# VCA.net
KiCad netlist of a schematic drawn in Altium Designer
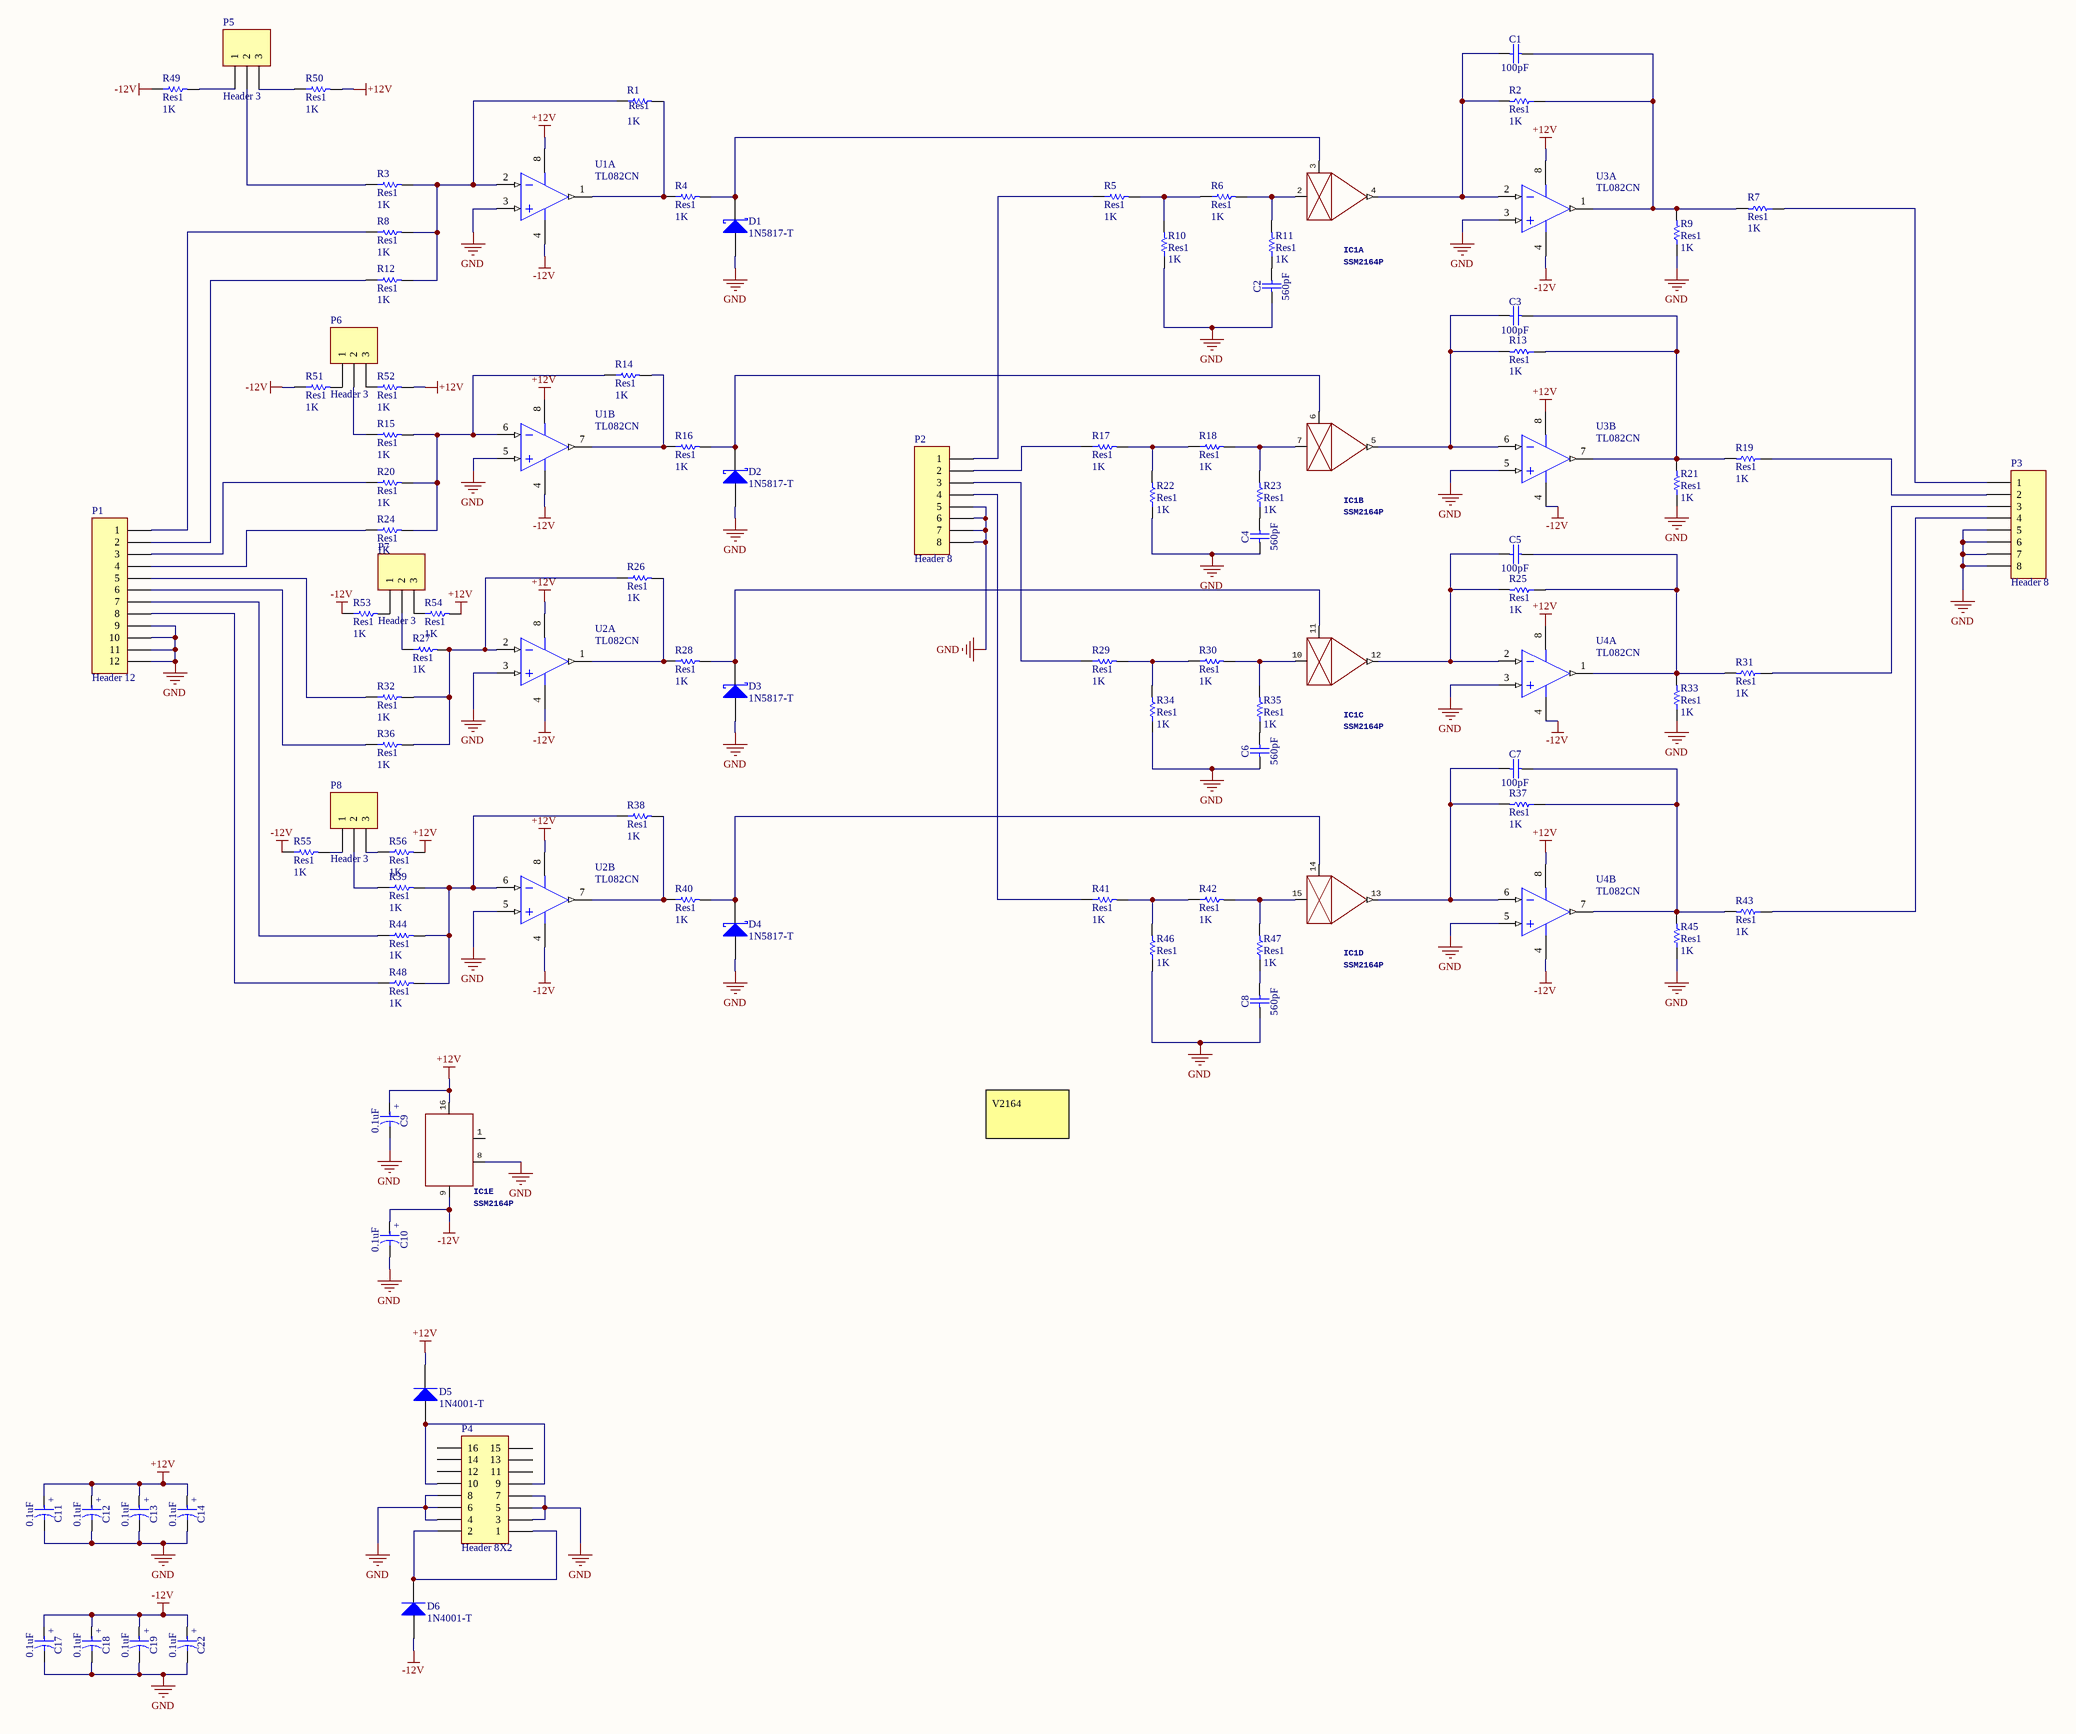
[diagram p0: VCA.SchDoc]

(export (version "E")
  (design (tool "Eeschema 10.0.6"))
  (components
    (comp (ref "C1")
      (value "100pF")
      (footprint "CAPRR508-254X381X584")
      (description "Non-polarised capacitor")
      (fields
        (field (name "PART NUMBER") "CCR_100PF_100V_5%_C0G_508-254X381X584")
        (field (name "VOLTAGE") "100VDC")
        (field (name "AUTHOR") "CERN DEM JLC")
      )
      (libsource (lib "Capacitors") (part "Capacitor - non polarized"))
    )
    (comp (ref "C2")
      (value "560pF")
      (footprint "CAPRR254-254X381X381")
      (description "Non-polarised capacitor")
      (fields
        (field (name "PART NUMBER") "CCR_560PF_100V_5%_C0G_254-254X381X381")
        (field (name "VOLTAGE") "100VDC")
        (field (name "AUTHOR") "CERN DEM JLC")
      )
      (libsource (lib "Capacitors") (part "Capacitor - non polarized"))
    )
    (comp (ref "C3")
      (value "100pF")
      (footprint "CAPRR508-254X381X584")
      (description "Non-polarised capacitor")
      (fields
        (field (name "PART NUMBER") "CCR_100PF_100V_5%_C0G_508-254X381X584")
        (field (name "VOLTAGE") "100VDC")
        (field (name "AUTHOR") "CERN DEM JLC")
      )
      (libsource (lib "Capacitors") (part "Capacitor - non polarized"))
    )
    (comp (ref "C4")
      (value "560pF")
      (footprint "CAPRR254-254X381X381")
      (description "Non-polarised capacitor")
      (fields
        (field (name "PART NUMBER") "CCR_560PF_100V_5%_C0G_254-254X381X381")
        (field (name "VOLTAGE") "100VDC")
        (field (name "AUTHOR") "CERN DEM JLC")
      )
      (libsource (lib "Capacitors") (part "Capacitor - non polarized"))
    )
    (comp (ref "C5")
      (value "100pF")
      (footprint "CAPRR508-254X381X584")
      (description "Non-polarised capacitor")
      (fields
        (field (name "PART NUMBER") "CCR_100PF_100V_5%_C0G_508-254X381X584")
        (field (name "VOLTAGE") "100VDC")
        (field (name "AUTHOR") "CERN DEM JLC")
      )
      (libsource (lib "Capacitors") (part "Capacitor - non polarized"))
    )
    (comp (ref "C6")
      (value "560pF")
      (footprint "CAPRR254-254X381X381")
      (description "Non-polarised capacitor")
      (fields
        (field (name "PART NUMBER") "CCR_560PF_100V_5%_C0G_254-254X381X381")
        (field (name "VOLTAGE") "100VDC")
        (field (name "AUTHOR") "CERN DEM JLC")
      )
      (libsource (lib "Capacitors") (part "Capacitor - non polarized"))
    )
    (comp (ref "C7")
      (value "100pF")
      (footprint "CAPRR508-254X381X584")
      (description "Non-polarised capacitor")
      (fields
        (field (name "PART NUMBER") "CCR_100PF_100V_5%_C0G_508-254X381X584")
        (field (name "VOLTAGE") "100VDC")
        (field (name "AUTHOR") "CERN DEM JLC")
      )
      (libsource (lib "Capacitors") (part "Capacitor - non polarized"))
    )
    (comp (ref "C8")
      (value "560pF")
      (footprint "CAPRR254-254X381X381")
      (description "Non-polarised capacitor")
      (fields
        (field (name "PART NUMBER") "CCR_560PF_100V_5%_C0G_254-254X381X381")
        (field (name "VOLTAGE") "100VDC")
        (field (name "AUTHOR") "CERN DEM JLC")
      )
      (libsource (lib "Capacitors") (part "Capacitor - non polarized"))
    )
    (comp (ref "C9")
      (value "0.1uF")
      (footprint "CAPPRB508-450x850")
      (description "Polarised capacitor")
      (fields
        (field (name "PART NUMBER") "CTEB_0.1UF_35V_10%_508-450X850")
        (field (name "VOLTAGE") "35V")
        (field (name "AUTHOR") "CERN DEM JLC")
      )
      (libsource (lib "Capacitors") (part "Capacitor - polarized"))
    )
    (comp (ref "C10")
      (value "0.1uF")
      (footprint "CAPPRB508-450x850")
      (description "Polarised capacitor")
      (fields
        (field (name "PART NUMBER") "CTEB_0.1UF_35V_10%_508-450X850")
        (field (name "VOLTAGE") "35V")
        (field (name "AUTHOR") "CERN DEM JLC")
      )
      (libsource (lib "Capacitors") (part "Capacitor - polarized"))
    )
    (comp (ref "C11")
      (value "0.1uF")
      (footprint "CAPPRB508-450x850")
      (description "Polarised capacitor")
      (fields
        (field (name "PART NUMBER") "CTEB_0.1UF_35V_10%_508-450X850")
        (field (name "VOLTAGE") "35V")
        (field (name "AUTHOR") "CERN DEM JLC")
      )
      (libsource (lib "Capacitors") (part "Capacitor - polarized"))
    )
    (comp (ref "C12")
      (value "0.1uF")
      (footprint "CAPPRB508-450x850")
      (description "Polarised capacitor")
      (fields
        (field (name "PART NUMBER") "CTEB_0.1UF_35V_10%_508-450X850")
        (field (name "VOLTAGE") "35V")
        (field (name "AUTHOR") "CERN DEM JLC")
      )
      (libsource (lib "Capacitors") (part "Capacitor - polarized"))
    )
    (comp (ref "C13")
      (value "0.1uF")
      (footprint "CAPPRB508-450x850")
      (description "Polarised capacitor")
      (fields
        (field (name "PART NUMBER") "CTEB_0.1UF_35V_10%_508-450X850")
        (field (name "VOLTAGE") "35V")
        (field (name "AUTHOR") "CERN DEM JLC")
      )
      (libsource (lib "Capacitors") (part "Capacitor - polarized"))
    )
    (comp (ref "C14")
      (value "0.1uF")
      (footprint "CAPPRB508-450x850")
      (description "Polarised capacitor")
      (fields
        (field (name "PART NUMBER") "CTEB_0.1UF_35V_10%_508-450X850")
        (field (name "VOLTAGE") "35V")
        (field (name "AUTHOR") "CERN DEM JLC")
      )
      (libsource (lib "Capacitors") (part "Capacitor - polarized"))
    )
    (comp (ref "C17")
      (value "0.1uF")
      (footprint "CAPPRB508-450x850")
      (description "Polarised capacitor")
      (fields
        (field (name "PART NUMBER") "CTEB_0.1UF_35V_10%_508-450X850")
        (field (name "VOLTAGE") "35V")
        (field (name "AUTHOR") "CERN DEM JLC")
      )
      (libsource (lib "Capacitors") (part "Capacitor - polarized"))
    )
    (comp (ref "C18")
      (value "0.1uF")
      (footprint "CAPPRB508-450x850")
      (description "Polarised capacitor")
      (fields
        (field (name "PART NUMBER") "CTEB_0.1UF_35V_10%_508-450X850")
        (field (name "VOLTAGE") "35V")
        (field (name "AUTHOR") "CERN DEM JLC")
      )
      (libsource (lib "Capacitors") (part "Capacitor - polarized"))
    )
    (comp (ref "C19")
      (value "0.1uF")
      (footprint "CAPPRB508-450x850")
      (description "Polarised capacitor")
      (fields
        (field (name "PART NUMBER") "CTEB_0.1UF_35V_10%_508-450X850")
        (field (name "VOLTAGE") "35V")
        (field (name "AUTHOR") "CERN DEM JLC")
      )
      (libsource (lib "Capacitors") (part "Capacitor - polarized"))
    )
    (comp (ref "C22")
      (value "0.1uF")
      (footprint "CAPPRB508-450x850")
      (description "Polarised capacitor")
      (fields
        (field (name "PART NUMBER") "CTEB_0.1UF_35V_10%_508-450X850")
        (field (name "VOLTAGE") "35V")
        (field (name "AUTHOR") "CERN DEM JLC")
      )
      (libsource (lib "Capacitors") (part "Capacitor - polarized"))
    )
    (comp (ref "D1")
      (value "1N5817-T")
      (footprint "DIOD-DO-41-P-2")
      (description "Schottky Barrier Rectifier, 1 A, 20 V, -65 to 125 degC, 2-Pin DO-41, RoHS, Tape and Reel")
      (fields (field (name "MANUFACTURER") "DiodesIncorporated"))
      (libsource (lib "Altium Content Vault") (part "DSKY-AK-2"))
    )
    (comp (ref "D2")
      (value "1N5817-T")
      (footprint "DIOD-DO-41-P-2")
      (description "Schottky Barrier Rectifier, 1 A, 20 V, -65 to 125 degC, 2-Pin DO-41, RoHS, Tape and Reel")
      (fields (field (name "MANUFACTURER") "DiodesIncorporated"))
      (libsource (lib "Altium Content Vault") (part "DSKY-AK-2"))
    )
    (comp (ref "D3")
      (value "1N5817-T")
      (footprint "DIOD-DO-41-P-2")
      (description "Schottky Barrier Rectifier, 1 A, 20 V, -65 to 125 degC, 2-Pin DO-41, RoHS, Tape and Reel")
      (fields (field (name "MANUFACTURER") "DiodesIncorporated"))
      (libsource (lib "Altium Content Vault") (part "DSKY-AK-2"))
    )
    (comp (ref "D4")
      (value "1N5817-T")
      (footprint "DIOD-DO-41-P-2")
      (description "Schottky Barrier Rectifier, 1 A, 20 V, -65 to 125 degC, 2-Pin DO-41, RoHS, Tape and Reel")
      (fields (field (name "MANUFACTURER") "DiodesIncorporated"))
      (libsource (lib "Altium Content Vault") (part "DSKY-AK-2"))
    )
    (comp (ref "D5")
      (value "1N4001-T")
      (footprint "DIOD-DO-41-P-2_V")
      (description "1.0 A Rectifier, 15 pF, 50 V, -65 to 150 degC, 2-Pin DO-41 Plastic, RoHS, Tape and Reel")
      (fields (field (name "MANUFACTURER") "Diodes Inc"))
      (libsource (lib "Altium Content Vault") (part "DIOD-D-A1K2-2"))
    )
    (comp (ref "D6")
      (value "1N4001-T")
      (footprint "DIOD-DO-41-P-2_V")
      (description "1.0 A Rectifier, 15 pF, 50 V, -65 to 150 degC, 2-Pin DO-41 Plastic, RoHS, Tape and Reel")
      (fields (field (name "MANUFACTURER") "Diodes Inc"))
      (libsource (lib "Altium Content Vault") (part "DIOD-D-A1K2-2"))
    )
    (comp (ref "IC1") (value "SSM2164P") (footprint "DIL16") (libsource (lib "ssm2164_2") (part "SSM2164P")))
    (comp (ref "P1")
      (value "Header 12")
      (footprint "HDR1X12")
      (description "Header, 12-Pin")
      (fields (field (name "PUBLISHER") "Altium Limited"))
      (libsource (lib "Miscellaneous Connectors") (part "Header 12"))
    )
    (comp (ref "P2")
      (value "Header 8")
      (footprint "HDR1X8")
      (description "Header, 8-Pin")
      (fields (field (name "PUBLISHER") "Altium Limited"))
      (libsource (lib "Miscellaneous Connectors") (part "Header 8"))
    )
    (comp (ref "P3")
      (value "Header 8")
      (footprint "HDR1X8")
      (description "Header, 8-Pin")
      (fields (field (name "PUBLISHER") "Altium Limited"))
      (libsource (lib "") (part "Header 8_1"))
    )
    (comp (ref "P4")
      (value "Header 8X2")
      (footprint "HDR2X8")
      (description "Header, 8-Pin, Dual row")
      (fields (field (name "PUBLISHER") "Altium Limited"))
      (libsource (lib "Miscellaneous Connectors") (part "Header 8X2"))
    )
    (comp (ref "P5")
      (value "Header 3")
      (footprint "HDR1X3")
      (description "Header, 3-Pin")
      (fields (field (name "PUBLISHER") "Altium Limited"))
      (libsource (lib "Miscellaneous Connectors") (part "Header 3"))
    )
    (comp (ref "P6")
      (value "Header 3")
      (footprint "HDR1X3")
      (description "Header, 3-Pin")
      (fields (field (name "PUBLISHER") "Altium Limited"))
      (libsource (lib "Miscellaneous Connectors") (part "Header 3"))
    )
    (comp (ref "P7")
      (value "Header 3")
      (footprint "HDR1X3")
      (description "Header, 3-Pin")
      (fields (field (name "PUBLISHER") "Altium Limited"))
      (libsource (lib "Miscellaneous Connectors") (part "Header 3"))
    )
    (comp (ref "P8")
      (value "Header 3")
      (footprint "HDR1X3")
      (description "Header, 3-Pin")
      (fields (field (name "PUBLISHER") "Altium Limited"))
      (libsource (lib "Miscellaneous Connectors") (part "Header 3"))
    )
    (comp (ref "R1")
      (value "Res1")
      (footprint "AXIAL-0.3")
      (description "Resistor")
      (fields (field (name "ALTIUM_VALUE") "1K") (field (name "PUBLISHER") "Altium Limited"))
      (libsource (lib "Miscellaneous Devices") (part "Res1"))
    )
    (comp (ref "R2")
      (value "Res1")
      (footprint "AXIAL-0.3")
      (description "Resistor")
      (fields (field (name "ALTIUM_VALUE") "1K") (field (name "PUBLISHER") "Altium Limited"))
      (libsource (lib "Miscellaneous Devices") (part "Res1"))
    )
    (comp (ref "R3")
      (value "Res1")
      (footprint "AXIAL-0.3")
      (description "Resistor")
      (fields (field (name "ALTIUM_VALUE") "1K") (field (name "PUBLISHER") "Altium Limited"))
      (libsource (lib "Miscellaneous Devices") (part "Res1"))
    )
    (comp (ref "R4")
      (value "Res1")
      (footprint "AXIAL-0.3")
      (description "Resistor")
      (fields (field (name "ALTIUM_VALUE") "1K") (field (name "PUBLISHER") "Altium Limited"))
      (libsource (lib "Miscellaneous Devices") (part "Res1"))
    )
    (comp (ref "R5")
      (value "Res1")
      (footprint "AXIAL-0.3")
      (description "Resistor")
      (fields (field (name "ALTIUM_VALUE") "1K") (field (name "PUBLISHER") "Altium Limited"))
      (libsource (lib "Miscellaneous Devices") (part "Res1"))
    )
    (comp (ref "R6")
      (value "Res1")
      (footprint "AXIAL-0.3")
      (description "Resistor")
      (fields (field (name "ALTIUM_VALUE") "1K") (field (name "PUBLISHER") "Altium Limited"))
      (libsource (lib "Miscellaneous Devices") (part "Res1"))
    )
    (comp (ref "R7")
      (value "Res1")
      (footprint "AXIAL-0.3")
      (description "Resistor")
      (fields (field (name "ALTIUM_VALUE") "1K") (field (name "PUBLISHER") "Altium Limited"))
      (libsource (lib "Miscellaneous Devices") (part "Res1"))
    )
    (comp (ref "R8")
      (value "Res1")
      (footprint "AXIAL-0.3")
      (description "Resistor")
      (fields (field (name "ALTIUM_VALUE") "1K") (field (name "PUBLISHER") "Altium Limited"))
      (libsource (lib "Miscellaneous Devices") (part "Res1"))
    )
    (comp (ref "R9")
      (value "Res1")
      (footprint "AXIAL-0.3")
      (description "Resistor")
      (fields (field (name "ALTIUM_VALUE") "1K") (field (name "PUBLISHER") "Altium Limited"))
      (libsource (lib "Miscellaneous Devices") (part "Res1"))
    )
    (comp (ref "R10")
      (value "Res1")
      (footprint "AXIAL-0.3")
      (description "Resistor")
      (fields (field (name "ALTIUM_VALUE") "1K") (field (name "PUBLISHER") "Altium Limited"))
      (libsource (lib "Miscellaneous Devices") (part "Res1"))
    )
    (comp (ref "R11")
      (value "Res1")
      (footprint "AXIAL-0.3")
      (description "Resistor")
      (fields (field (name "ALTIUM_VALUE") "1K") (field (name "PUBLISHER") "Altium Limited"))
      (libsource (lib "Miscellaneous Devices") (part "Res1"))
    )
    (comp (ref "R12")
      (value "Res1")
      (footprint "AXIAL-0.3")
      (description "Resistor")
      (fields (field (name "ALTIUM_VALUE") "1K") (field (name "PUBLISHER") "Altium Limited"))
      (libsource (lib "Miscellaneous Devices") (part "Res1"))
    )
    (comp (ref "R13")
      (value "Res1")
      (footprint "AXIAL-0.3")
      (description "Resistor")
      (fields (field (name "ALTIUM_VALUE") "1K") (field (name "PUBLISHER") "Altium Limited"))
      (libsource (lib "Miscellaneous Devices") (part "Res1"))
    )
    (comp (ref "R14")
      (value "Res1")
      (footprint "AXIAL-0.3")
      (description "Resistor")
      (fields (field (name "ALTIUM_VALUE") "1K") (field (name "PUBLISHER") "Altium Limited"))
      (libsource (lib "Miscellaneous Devices") (part "Res1"))
    )
    (comp (ref "R15")
      (value "Res1")
      (footprint "AXIAL-0.3")
      (description "Resistor")
      (fields (field (name "ALTIUM_VALUE") "1K") (field (name "PUBLISHER") "Altium Limited"))
      (libsource (lib "Miscellaneous Devices") (part "Res1"))
    )
    (comp (ref "R16")
      (value "Res1")
      (footprint "AXIAL-0.3")
      (description "Resistor")
      (fields (field (name "ALTIUM_VALUE") "1K") (field (name "PUBLISHER") "Altium Limited"))
      (libsource (lib "Miscellaneous Devices") (part "Res1"))
    )
    (comp (ref "R17")
      (value "Res1")
      (footprint "AXIAL-0.3")
      (description "Resistor")
      (fields (field (name "ALTIUM_VALUE") "1K") (field (name "PUBLISHER") "Altium Limited"))
      (libsource (lib "Miscellaneous Devices") (part "Res1"))
    )
    (comp (ref "R18")
      (value "Res1")
      (footprint "AXIAL-0.3")
      (description "Resistor")
      (fields (field (name "ALTIUM_VALUE") "1K") (field (name "PUBLISHER") "Altium Limited"))
      (libsource (lib "Miscellaneous Devices") (part "Res1"))
    )
    (comp (ref "R19")
      (value "Res1")
      (footprint "AXIAL-0.3")
      (description "Resistor")
      (fields (field (name "ALTIUM_VALUE") "1K") (field (name "PUBLISHER") "Altium Limited"))
      (libsource (lib "Miscellaneous Devices") (part "Res1"))
    )
    (comp (ref "R20")
      (value "Res1")
      (footprint "AXIAL-0.3")
      (description "Resistor")
      (fields (field (name "ALTIUM_VALUE") "1K") (field (name "PUBLISHER") "Altium Limited"))
      (libsource (lib "Miscellaneous Devices") (part "Res1"))
    )
    (comp (ref "R21")
      (value "Res1")
      (footprint "AXIAL-0.3")
      (description "Resistor")
      (fields (field (name "ALTIUM_VALUE") "1K") (field (name "PUBLISHER") "Altium Limited"))
      (libsource (lib "Miscellaneous Devices") (part "Res1"))
    )
    (comp (ref "R22")
      (value "Res1")
      (footprint "AXIAL-0.3")
      (description "Resistor")
      (fields (field (name "ALTIUM_VALUE") "1K") (field (name "PUBLISHER") "Altium Limited"))
      (libsource (lib "Miscellaneous Devices") (part "Res1"))
    )
    (comp (ref "R23")
      (value "Res1")
      (footprint "AXIAL-0.3")
      (description "Resistor")
      (fields (field (name "ALTIUM_VALUE") "1K") (field (name "PUBLISHER") "Altium Limited"))
      (libsource (lib "Miscellaneous Devices") (part "Res1"))
    )
    (comp (ref "R24")
      (value "Res1")
      (footprint "AXIAL-0.3")
      (description "Resistor")
      (fields (field (name "ALTIUM_VALUE") "1K") (field (name "PUBLISHER") "Altium Limited"))
      (libsource (lib "Miscellaneous Devices") (part "Res1"))
    )
    (comp (ref "R25")
      (value "Res1")
      (footprint "AXIAL-0.3")
      (description "Resistor")
      (fields (field (name "ALTIUM_VALUE") "1K") (field (name "PUBLISHER") "Altium Limited"))
      (libsource (lib "Miscellaneous Devices") (part "Res1"))
    )
    (comp (ref "R26")
      (value "Res1")
      (footprint "AXIAL-0.3")
      (description "Resistor")
      (fields (field (name "ALTIUM_VALUE") "1K") (field (name "PUBLISHER") "Altium Limited"))
      (libsource (lib "Miscellaneous Devices") (part "Res1"))
    )
    (comp (ref "R27")
      (value "Res1")
      (footprint "AXIAL-0.3")
      (description "Resistor")
      (fields (field (name "ALTIUM_VALUE") "1K") (field (name "PUBLISHER") "Altium Limited"))
      (libsource (lib "Miscellaneous Devices") (part "Res1"))
    )
    (comp (ref "R28")
      (value "Res1")
      (footprint "AXIAL-0.3")
      (description "Resistor")
      (fields (field (name "ALTIUM_VALUE") "1K") (field (name "PUBLISHER") "Altium Limited"))
      (libsource (lib "Miscellaneous Devices") (part "Res1"))
    )
    (comp (ref "R29")
      (value "Res1")
      (footprint "AXIAL-0.3")
      (description "Resistor")
      (fields (field (name "ALTIUM_VALUE") "1K") (field (name "PUBLISHER") "Altium Limited"))
      (libsource (lib "Miscellaneous Devices") (part "Res1"))
    )
    (comp (ref "R30")
      (value "Res1")
      (footprint "AXIAL-0.3")
      (description "Resistor")
      (fields (field (name "ALTIUM_VALUE") "1K") (field (name "PUBLISHER") "Altium Limited"))
      (libsource (lib "Miscellaneous Devices") (part "Res1"))
    )
    (comp (ref "R31")
      (value "Res1")
      (footprint "AXIAL-0.3")
      (description "Resistor")
      (fields (field (name "ALTIUM_VALUE") "1K") (field (name "PUBLISHER") "Altium Limited"))
      (libsource (lib "Miscellaneous Devices") (part "Res1"))
    )
    (comp (ref "R32")
      (value "Res1")
      (footprint "AXIAL-0.3")
      (description "Resistor")
      (fields (field (name "ALTIUM_VALUE") "1K") (field (name "PUBLISHER") "Altium Limited"))
      (libsource (lib "Miscellaneous Devices") (part "Res1"))
    )
    (comp (ref "R33")
      (value "Res1")
      (footprint "AXIAL-0.3")
      (description "Resistor")
      (fields (field (name "ALTIUM_VALUE") "1K") (field (name "PUBLISHER") "Altium Limited"))
      (libsource (lib "Miscellaneous Devices") (part "Res1"))
    )
    (comp (ref "R34")
      (value "Res1")
      (footprint "AXIAL-0.3")
      (description "Resistor")
      (fields (field (name "ALTIUM_VALUE") "1K") (field (name "PUBLISHER") "Altium Limited"))
      (libsource (lib "Miscellaneous Devices") (part "Res1"))
    )
    (comp (ref "R35")
      (value "Res1")
      (footprint "AXIAL-0.3")
      (description "Resistor")
      (fields (field (name "ALTIUM_VALUE") "1K") (field (name "PUBLISHER") "Altium Limited"))
      (libsource (lib "Miscellaneous Devices") (part "Res1"))
    )
    (comp (ref "R36")
      (value "Res1")
      (footprint "AXIAL-0.3")
      (description "Resistor")
      (fields (field (name "ALTIUM_VALUE") "1K") (field (name "PUBLISHER") "Altium Limited"))
      (libsource (lib "Miscellaneous Devices") (part "Res1"))
    )
    (comp (ref "R37")
      (value "Res1")
      (footprint "AXIAL-0.3")
      (description "Resistor")
      (fields (field (name "ALTIUM_VALUE") "1K") (field (name "PUBLISHER") "Altium Limited"))
      (libsource (lib "Miscellaneous Devices") (part "Res1"))
    )
    (comp (ref "R38")
      (value "Res1")
      (footprint "AXIAL-0.3")
      (description "Resistor")
      (fields (field (name "ALTIUM_VALUE") "1K") (field (name "PUBLISHER") "Altium Limited"))
      (libsource (lib "Miscellaneous Devices") (part "Res1"))
    )
    (comp (ref "R39")
      (value "Res1")
      (footprint "AXIAL-0.3")
      (description "Resistor")
      (fields (field (name "ALTIUM_VALUE") "1K") (field (name "PUBLISHER") "Altium Limited"))
      (libsource (lib "Miscellaneous Devices") (part "Res1"))
    )
    (comp (ref "R40")
      (value "Res1")
      (footprint "AXIAL-0.3")
      (description "Resistor")
      (fields (field (name "ALTIUM_VALUE") "1K") (field (name "PUBLISHER") "Altium Limited"))
      (libsource (lib "Miscellaneous Devices") (part "Res1"))
    )
    (comp (ref "R41")
      (value "Res1")
      (footprint "AXIAL-0.3")
      (description "Resistor")
      (fields (field (name "ALTIUM_VALUE") "1K") (field (name "PUBLISHER") "Altium Limited"))
      (libsource (lib "Miscellaneous Devices") (part "Res1"))
    )
    (comp (ref "R42")
      (value "Res1")
      (footprint "AXIAL-0.3")
      (description "Resistor")
      (fields (field (name "ALTIUM_VALUE") "1K") (field (name "PUBLISHER") "Altium Limited"))
      (libsource (lib "Miscellaneous Devices") (part "Res1"))
    )
    (comp (ref "R43")
      (value "Res1")
      (footprint "AXIAL-0.3")
      (description "Resistor")
      (fields (field (name "ALTIUM_VALUE") "1K") (field (name "PUBLISHER") "Altium Limited"))
      (libsource (lib "Miscellaneous Devices") (part "Res1"))
    )
    (comp (ref "R44")
      (value "Res1")
      (footprint "AXIAL-0.3")
      (description "Resistor")
      (fields (field (name "ALTIUM_VALUE") "1K") (field (name "PUBLISHER") "Altium Limited"))
      (libsource (lib "Miscellaneous Devices") (part "Res1"))
    )
    (comp (ref "R45")
      (value "Res1")
      (footprint "AXIAL-0.3")
      (description "Resistor")
      (fields (field (name "ALTIUM_VALUE") "1K") (field (name "PUBLISHER") "Altium Limited"))
      (libsource (lib "Miscellaneous Devices") (part "Res1"))
    )
    (comp (ref "R46")
      (value "Res1")
      (footprint "AXIAL-0.3")
      (description "Resistor")
      (fields (field (name "ALTIUM_VALUE") "1K") (field (name "PUBLISHER") "Altium Limited"))
      (libsource (lib "Miscellaneous Devices") (part "Res1"))
    )
    (comp (ref "R47")
      (value "Res1")
      (footprint "AXIAL-0.3")
      (description "Resistor")
      (fields (field (name "ALTIUM_VALUE") "1K") (field (name "PUBLISHER") "Altium Limited"))
      (libsource (lib "Miscellaneous Devices") (part "Res1"))
    )
    (comp (ref "R48")
      (value "Res1")
      (footprint "AXIAL-0.3")
      (description "Resistor")
      (fields (field (name "ALTIUM_VALUE") "1K") (field (name "PUBLISHER") "Altium Limited"))
      (libsource (lib "Miscellaneous Devices") (part "Res1"))
    )
    (comp (ref "R49")
      (value "Res1")
      (footprint "AXIAL-0.3")
      (description "Resistor")
      (fields (field (name "ALTIUM_VALUE") "1K") (field (name "PUBLISHER") "Altium Limited"))
      (libsource (lib "Miscellaneous Devices") (part "Res1"))
    )
    (comp (ref "R50")
      (value "Res1")
      (footprint "AXIAL-0.3")
      (description "Resistor")
      (fields (field (name "ALTIUM_VALUE") "1K") (field (name "PUBLISHER") "Altium Limited"))
      (libsource (lib "Miscellaneous Devices") (part "Res1"))
    )
    (comp (ref "R51")
      (value "Res1")
      (footprint "AXIAL-0.3")
      (description "Resistor")
      (fields (field (name "ALTIUM_VALUE") "1K") (field (name "PUBLISHER") "Altium Limited"))
      (libsource (lib "Miscellaneous Devices") (part "Res1"))
    )
    (comp (ref "R52")
      (value "Res1")
      (footprint "AXIAL-0.3")
      (description "Resistor")
      (fields (field (name "ALTIUM_VALUE") "1K") (field (name "PUBLISHER") "Altium Limited"))
      (libsource (lib "Miscellaneous Devices") (part "Res1"))
    )
    (comp (ref "R53")
      (value "Res1")
      (footprint "AXIAL-0.3")
      (description "Resistor")
      (fields (field (name "ALTIUM_VALUE") "1K") (field (name "PUBLISHER") "Altium Limited"))
      (libsource (lib "Miscellaneous Devices") (part "Res1"))
    )
    (comp (ref "R54")
      (value "Res1")
      (footprint "AXIAL-0.3")
      (description "Resistor")
      (fields (field (name "ALTIUM_VALUE") "1K") (field (name "PUBLISHER") "Altium Limited"))
      (libsource (lib "Miscellaneous Devices") (part "Res1"))
    )
    (comp (ref "R55")
      (value "Res1")
      (footprint "AXIAL-0.3")
      (description "Resistor")
      (fields (field (name "ALTIUM_VALUE") "1K") (field (name "PUBLISHER") "Altium Limited"))
      (libsource (lib "Miscellaneous Devices") (part "Res1"))
    )
    (comp (ref "R56")
      (value "Res1")
      (footprint "AXIAL-0.3")
      (description "Resistor")
      (fields (field (name "ALTIUM_VALUE") "1K") (field (name "PUBLISHER") "Altium Limited"))
      (libsource (lib "Miscellaneous Devices") (part "Res1"))
    )
    (comp (ref "U1")
      (value "TL082CN")
      (footprint "STM-N8")
      (fields (field (name "MANUFACTURER") "STMicroelectronics"))
      (libsource (lib "Altium Content Vault") (part "STM-TL082-N8"))
    )
    (comp (ref "U2")
      (value "TL082CN")
      (footprint "STM-N8")
      (fields (field (name "MANUFACTURER") "STMicroelectronics"))
      (libsource (lib "Altium Content Vault") (part "STM-TL082-N8"))
    )
    (comp (ref "U3")
      (value "TL082CN")
      (footprint "STM-N8")
      (fields (field (name "MANUFACTURER") "STMicroelectronics"))
      (libsource (lib "Altium Content Vault") (part "STM-TL082-N8"))
    )
    (comp (ref "U4")
      (value "TL082CN")
      (footprint "STM-N8")
      (fields (field (name "MANUFACTURER") "STMicroelectronics"))
      (libsource (lib "Altium Content Vault") (part "STM-TL082-N8"))
    )
  )
  (nets
    (net (code "1") (name "+12V") (class "Default")
      (node (ref "C11") (pin "1") (pinfunction "1_1") (pintype "passive"))
      (node (ref "C12") (pin "1") (pinfunction "1_1") (pintype "passive"))
      (node (ref "C13") (pin "1") (pinfunction "1_1") (pintype "passive"))
      (node (ref "C14") (pin "1") (pinfunction "1_1") (pintype "passive"))
      (node (ref "C9") (pin "1") (pinfunction "1_1") (pintype "passive"))
      (node (ref "D5") (pin "2") (pinfunction "K_2") (pintype "passive"))
      (node (ref "IC1") (pin "16") (pinfunction "V+_16") (pintype "power_in"))
      (node (ref "R50") (pin "2") (pinfunction "2_2") (pintype "passive"))
      (node (ref "R52") (pin "2") (pinfunction "2_2") (pintype "passive"))
      (node (ref "R54") (pin "2") (pinfunction "2_2") (pintype "passive"))
      (node (ref "R56") (pin "2") (pinfunction "2_2") (pintype "passive"))
      (node (ref "U1") (pin "8") (pinfunction "VCC+_8") (pintype "power_in"))
      (node (ref "U2") (pin "8") (pinfunction "VCC+_8") (pintype "power_in"))
      (node (ref "U3") (pin "8") (pinfunction "VCC+_8") (pintype "power_in"))
      (node (ref "U4") (pin "8") (pinfunction "VCC+_8") (pintype "power_in"))
    )
    (net (code "2") (name "-12V") (class "Default")
      (node (ref "C10") (pin "1") (pinfunction "1_1") (pintype "passive"))
      (node (ref "C17") (pin "1") (pinfunction "1_1") (pintype "passive"))
      (node (ref "C18") (pin "1") (pinfunction "1_1") (pintype "passive"))
      (node (ref "C19") (pin "1") (pinfunction "1_1") (pintype "passive"))
      (node (ref "C22") (pin "1") (pinfunction "1_1") (pintype "passive"))
      (node (ref "D6") (pin "1") (pinfunction "A_1") (pintype "passive"))
      (node (ref "IC1") (pin "9") (pinfunction "V-_9") (pintype "power_in"))
      (node (ref "R49") (pin "1") (pinfunction "1_1") (pintype "passive"))
      (node (ref "R51") (pin "1") (pinfunction "1_1") (pintype "passive"))
      (node (ref "R53") (pin "1") (pinfunction "1_1") (pintype "passive"))
      (node (ref "R55") (pin "1") (pinfunction "1_1") (pintype "passive"))
      (node (ref "U1") (pin "4") (pinfunction "VCC-_4") (pintype "power_in"))
      (node (ref "U2") (pin "4") (pinfunction "VCC-_4") (pintype "power_in"))
      (node (ref "U3") (pin "4") (pinfunction "VCC-_4") (pintype "power_in"))
      (node (ref "U4") (pin "4") (pinfunction "VCC-_4") (pintype "power_in"))
    )
    (net (code "3") (name "GND") (class "Default")
      (node (ref "C10") (pin "2") (pinfunction "2_2") (pintype "passive"))
      (node (ref "C11") (pin "2") (pinfunction "2_2") (pintype "passive"))
      (node (ref "C12") (pin "2") (pinfunction "2_2") (pintype "passive"))
      (node (ref "C13") (pin "2") (pinfunction "2_2") (pintype "passive"))
      (node (ref "C14") (pin "2") (pinfunction "2_2") (pintype "passive"))
      (node (ref "C17") (pin "2") (pinfunction "2_2") (pintype "passive"))
      (node (ref "C18") (pin "2") (pinfunction "2_2") (pintype "passive"))
      (node (ref "C19") (pin "2") (pinfunction "2_2") (pintype "passive"))
      (node (ref "C2") (pin "1") (pinfunction "1_1") (pintype "passive"))
      (node (ref "C22") (pin "2") (pinfunction "2_2") (pintype "passive"))
      (node (ref "C4") (pin "1") (pinfunction "1_1") (pintype "passive"))
      (node (ref "C6") (pin "1") (pinfunction "1_1") (pintype "passive"))
      (node (ref "C8") (pin "1") (pinfunction "1_1") (pintype "passive"))
      (node (ref "C9") (pin "2") (pinfunction "2_2") (pintype "passive"))
      (node (ref "D1") (pin "1") (pinfunction "A_1") (pintype "passive"))
      (node (ref "D2") (pin "1") (pinfunction "A_1") (pintype "passive"))
      (node (ref "D3") (pin "1") (pinfunction "A_1") (pintype "passive"))
      (node (ref "D4") (pin "1") (pinfunction "A_1") (pintype "passive"))
      (node (ref "IC1") (pin "8") (pinfunction "GND_8") (pintype "power_in"))
      (node (ref "P1") (pin "10") (pinfunction "10_10") (pintype "passive"))
      (node (ref "P1") (pin "11") (pinfunction "11_11") (pintype "passive"))
      (node (ref "P1") (pin "12") (pinfunction "12_12") (pintype "passive"))
      (node (ref "P1") (pin "9") (pinfunction "9_9") (pintype "passive"))
      (node (ref "P2") (pin "5") (pinfunction "5_5") (pintype "passive"))
      (node (ref "P2") (pin "6") (pinfunction "6_6") (pintype "passive"))
      (node (ref "P2") (pin "7") (pinfunction "7_7") (pintype "passive"))
      (node (ref "P2") (pin "8") (pinfunction "8_8") (pintype "passive"))
      (node (ref "P3") (pin "5") (pinfunction "5_5") (pintype "passive"))
      (node (ref "P3") (pin "6") (pinfunction "6_6") (pintype "passive"))
      (node (ref "P3") (pin "7") (pinfunction "7_7") (pintype "passive"))
      (node (ref "P3") (pin "8") (pinfunction "8_8") (pintype "passive"))
      (node (ref "P4") (pin "3") (pinfunction "3_3") (pintype "passive"))
      (node (ref "P4") (pin "4") (pinfunction "4_4") (pintype "passive"))
      (node (ref "P4") (pin "5") (pinfunction "5_5") (pintype "passive"))
      (node (ref "P4") (pin "6") (pinfunction "6_6") (pintype "passive"))
      (node (ref "P4") (pin "7") (pinfunction "7_7") (pintype "passive"))
      (node (ref "P4") (pin "8") (pinfunction "8_8") (pintype "passive"))
      (node (ref "R10") (pin "1") (pinfunction "1_1") (pintype "passive"))
      (node (ref "R21") (pin "1") (pinfunction "1_1") (pintype "passive"))
      (node (ref "R22") (pin "1") (pinfunction "1_1") (pintype "passive"))
      (node (ref "R33") (pin "1") (pinfunction "1_1") (pintype "passive"))
      (node (ref "R34") (pin "1") (pinfunction "1_1") (pintype "passive"))
      (node (ref "R45") (pin "1") (pinfunction "1_1") (pintype "passive"))
      (node (ref "R46") (pin "1") (pinfunction "1_1") (pintype "passive"))
      (node (ref "R9") (pin "1") (pinfunction "1_1") (pintype "passive"))
      (node (ref "U1") (pin "3") (pinfunction "IN1+_3") (pintype "input"))
      (node (ref "U1") (pin "5") (pinfunction "IN2+_5") (pintype "input"))
      (node (ref "U2") (pin "3") (pinfunction "IN1+_3") (pintype "input"))
      (node (ref "U2") (pin "5") (pinfunction "IN2+_5") (pintype "input"))
      (node (ref "U3") (pin "3") (pinfunction "IN1+_3") (pintype "input"))
      (node (ref "U3") (pin "5") (pinfunction "IN2+_5") (pintype "input"))
      (node (ref "U4") (pin "3") (pinfunction "IN1+_3") (pintype "input"))
      (node (ref "U4") (pin "5") (pinfunction "IN2+_5") (pintype "input"))
    )
    (net (code "4") (name "Net-(C2-Pad2)") (class "Default")
      (node (ref "C2") (pin "2") (pinfunction "2_2") (pintype "passive"))
      (node (ref "R11") (pin "1") (pinfunction "1_1") (pintype "passive"))
    )
    (net (code "5") (name "Net-(C4-Pad2)") (class "Default")
      (node (ref "C4") (pin "2") (pinfunction "2_2") (pintype "passive"))
      (node (ref "R23") (pin "1") (pinfunction "1_1") (pintype "passive"))
    )
    (net (code "6") (name "Net-(C6-Pad2)") (class "Default")
      (node (ref "C6") (pin "2") (pinfunction "2_2") (pintype "passive"))
      (node (ref "R35") (pin "1") (pinfunction "1_1") (pintype "passive"))
    )
    (net (code "7") (name "Net-(C8-Pad2)") (class "Default")
      (node (ref "C8") (pin "2") (pinfunction "2_2") (pintype "passive"))
      (node (ref "R47") (pin "1") (pinfunction "1_1") (pintype "passive"))
    )
    (net (code "8") (name "Net-(D1-K)") (class "Default")
      (node (ref "D1") (pin "2") (pinfunction "K_2") (pintype "passive"))
      (node (ref "IC1") (pin "3") (pinfunction "CTRL_3") (pintype "passive"))
      (node (ref "R4") (pin "2") (pinfunction "2_2") (pintype "passive"))
    )
    (net (code "9") (name "Net-(D2-K)") (class "Default")
      (node (ref "D2") (pin "2") (pinfunction "K_2") (pintype "passive"))
      (node (ref "IC1") (pin "6") (pinfunction "CTRL_6") (pintype "passive"))
      (node (ref "R16") (pin "2") (pinfunction "2_2") (pintype "passive"))
    )
    (net (code "10") (name "Net-(D3-K)") (class "Default")
      (node (ref "D3") (pin "2") (pinfunction "K_2") (pintype "passive"))
      (node (ref "IC1") (pin "11") (pinfunction "CTRL_11") (pintype "passive"))
      (node (ref "R28") (pin "2") (pinfunction "2_2") (pintype "passive"))
    )
    (net (code "11") (name "Net-(D4-K)") (class "Default")
      (node (ref "D4") (pin "2") (pinfunction "K_2") (pintype "passive"))
      (node (ref "IC1") (pin "14") (pinfunction "CTRL_14") (pintype "passive"))
      (node (ref "R40") (pin "2") (pinfunction "2_2") (pintype "passive"))
    )
    (net (code "12") (name "Net-(D5-A)") (class "Default")
      (node (ref "D5") (pin "1") (pinfunction "A_1") (pintype "passive"))
      (node (ref "P4") (pin "10") (pinfunction "10_10") (pintype "passive"))
      (node (ref "P4") (pin "9") (pinfunction "9_9") (pintype "passive"))
    )
    (net (code "13") (name "Net-(D6-K)") (class "Default")
      (node (ref "D6") (pin "2") (pinfunction "K_2") (pintype "passive"))
      (node (ref "P4") (pin "1") (pinfunction "1_1") (pintype "passive"))
      (node (ref "P4") (pin "2") (pinfunction "2_2") (pintype "passive"))
    )
    (net (code "14") (name "Net-(IC1A-IN)") (class "Default")
      (node (ref "IC1") (pin "2") (pinfunction "IN_2") (pintype "passive"))
      (node (ref "R11") (pin "2") (pinfunction "2_2") (pintype "passive"))
      (node (ref "R6") (pin "2") (pinfunction "2_2") (pintype "passive"))
    )
    (net (code "15") (name "Net-(IC1A-OUT)") (class "Default")
      (node (ref "C1") (pin "1") (pinfunction "1_1") (pintype "passive"))
      (node (ref "IC1") (pin "4") (pinfunction "OUT_4") (pintype "output"))
      (node (ref "R2") (pin "2") (pinfunction "2_2") (pintype "passive"))
      (node (ref "U3") (pin "2") (pinfunction "IN1-_2") (pintype "input"))
    )
    (net (code "16") (name "Net-(IC1B-IN)") (class "Default")
      (node (ref "IC1") (pin "7") (pinfunction "IN_7") (pintype "passive"))
      (node (ref "R18") (pin "2") (pinfunction "2_2") (pintype "passive"))
      (node (ref "R23") (pin "2") (pinfunction "2_2") (pintype "passive"))
    )
    (net (code "17") (name "Net-(IC1B-OUT)") (class "Default")
      (node (ref "C3") (pin "1") (pinfunction "1_1") (pintype "passive"))
      (node (ref "IC1") (pin "5") (pinfunction "OUT_5") (pintype "output"))
      (node (ref "R13") (pin "2") (pinfunction "2_2") (pintype "passive"))
      (node (ref "U3") (pin "6") (pinfunction "IN2-_6") (pintype "input"))
    )
    (net (code "18") (name "Net-(IC1C-IN)") (class "Default")
      (node (ref "IC1") (pin "10") (pinfunction "IN_10") (pintype "passive"))
      (node (ref "R30") (pin "2") (pinfunction "2_2") (pintype "passive"))
      (node (ref "R35") (pin "2") (pinfunction "2_2") (pintype "passive"))
    )
    (net (code "19") (name "Net-(IC1C-OUT)") (class "Default")
      (node (ref "C5") (pin "1") (pinfunction "1_1") (pintype "passive"))
      (node (ref "IC1") (pin "12") (pinfunction "OUT_12") (pintype "output"))
      (node (ref "R25") (pin "2") (pinfunction "2_2") (pintype "passive"))
      (node (ref "U4") (pin "2") (pinfunction "IN1-_2") (pintype "input"))
    )
    (net (code "20") (name "Net-(IC1D-IN)") (class "Default")
      (node (ref "IC1") (pin "15") (pinfunction "IN_15") (pintype "passive"))
      (node (ref "R42") (pin "2") (pinfunction "2_2") (pintype "passive"))
      (node (ref "R47") (pin "2") (pinfunction "2_2") (pintype "passive"))
    )
    (net (code "21") (name "Net-(IC1D-OUT)") (class "Default")
      (node (ref "C7") (pin "1") (pinfunction "1_1") (pintype "passive"))
      (node (ref "IC1") (pin "13") (pinfunction "OUT_13") (pintype "output"))
      (node (ref "R37") (pin "2") (pinfunction "2_2") (pintype "passive"))
      (node (ref "U4") (pin "6") (pinfunction "IN2-_6") (pintype "input"))
    )
    (net (code "22") (name "Net-(P1-Pad1)") (class "Default")
      (node (ref "P1") (pin "1") (pinfunction "1_1") (pintype "passive"))
      (node (ref "R8") (pin "1") (pinfunction "1_1") (pintype "passive"))
    )
    (net (code "23") (name "Net-(P1-Pad2)") (class "Default")
      (node (ref "P1") (pin "2") (pinfunction "2_2") (pintype "passive"))
      (node (ref "R12") (pin "1") (pinfunction "1_1") (pintype "passive"))
    )
    (net (code "24") (name "Net-(P1-Pad3)") (class "Default")
      (node (ref "P1") (pin "3") (pinfunction "3_3") (pintype "passive"))
      (node (ref "R20") (pin "1") (pinfunction "1_1") (pintype "passive"))
    )
    (net (code "25") (name "Net-(P1-Pad4)") (class "Default")
      (node (ref "P1") (pin "4") (pinfunction "4_4") (pintype "passive"))
      (node (ref "R24") (pin "1") (pinfunction "1_1") (pintype "passive"))
    )
    (net (code "26") (name "Net-(P1-Pad5)") (class "Default")
      (node (ref "P1") (pin "5") (pinfunction "5_5") (pintype "passive"))
      (node (ref "R32") (pin "1") (pinfunction "1_1") (pintype "passive"))
    )
    (net (code "27") (name "Net-(P1-Pad6)") (class "Default")
      (node (ref "P1") (pin "6") (pinfunction "6_6") (pintype "passive"))
      (node (ref "R36") (pin "1") (pinfunction "1_1") (pintype "passive"))
    )
    (net (code "28") (name "Net-(P1-Pad7)") (class "Default")
      (node (ref "P1") (pin "7") (pinfunction "7_7") (pintype "passive"))
      (node (ref "R44") (pin "1") (pinfunction "1_1") (pintype "passive"))
    )
    (net (code "29") (name "Net-(P1-Pad8)") (class "Default")
      (node (ref "P1") (pin "8") (pinfunction "8_8") (pintype "passive"))
      (node (ref "R48") (pin "1") (pinfunction "1_1") (pintype "passive"))
    )
    (net (code "30") (name "Net-(P2-Pad1)") (class "Default")
      (node (ref "P2") (pin "1") (pinfunction "1_1") (pintype "passive"))
      (node (ref "R5") (pin "1") (pinfunction "1_1") (pintype "passive"))
    )
    (net (code "31") (name "Net-(P2-Pad2)") (class "Default")
      (node (ref "P2") (pin "2") (pinfunction "2_2") (pintype "passive"))
      (node (ref "R17") (pin "1") (pinfunction "1_1") (pintype "passive"))
    )
    (net (code "32") (name "Net-(P2-Pad3)") (class "Default")
      (node (ref "P2") (pin "3") (pinfunction "3_3") (pintype "passive"))
      (node (ref "R29") (pin "1") (pinfunction "1_1") (pintype "passive"))
    )
    (net (code "33") (name "Net-(P2-Pad4)") (class "Default")
      (node (ref "P2") (pin "4") (pinfunction "4_4") (pintype "passive"))
      (node (ref "R41") (pin "1") (pinfunction "1_1") (pintype "passive"))
    )
    (net (code "34") (name "Net-(P3-Pad1)") (class "Default")
      (node (ref "P3") (pin "1") (pinfunction "1_1") (pintype "passive"))
      (node (ref "R7") (pin "1") (pinfunction "1_1") (pintype "passive"))
    )
    (net (code "35") (name "Net-(P3-Pad2)") (class "Default")
      (node (ref "P3") (pin "2") (pinfunction "2_2") (pintype "passive"))
      (node (ref "R19") (pin "1") (pinfunction "1_1") (pintype "passive"))
    )
    (net (code "36") (name "Net-(P3-Pad3)") (class "Default")
      (node (ref "P3") (pin "3") (pinfunction "3_3") (pintype "passive"))
      (node (ref "R31") (pin "1") (pinfunction "1_1") (pintype "passive"))
    )
    (net (code "37") (name "Net-(P3-Pad4)") (class "Default")
      (node (ref "P3") (pin "4") (pinfunction "4_4") (pintype "passive"))
      (node (ref "R43") (pin "1") (pinfunction "1_1") (pintype "passive"))
    )
    (net (code "38") (name "Net-(P5-Pad1)") (class "Default")
      (node (ref "P5") (pin "1") (pinfunction "1_1") (pintype "passive"))
      (node (ref "R49") (pin "2") (pinfunction "2_2") (pintype "passive"))
    )
    (net (code "39") (name "Net-(P5-Pad2)") (class "Default")
      (node (ref "P5") (pin "2") (pinfunction "2_2") (pintype "passive"))
      (node (ref "R3") (pin "1") (pinfunction "1_1") (pintype "passive"))
    )
    (net (code "40") (name "Net-(P5-Pad3)") (class "Default")
      (node (ref "P5") (pin "3") (pinfunction "3_3") (pintype "passive"))
      (node (ref "R50") (pin "1") (pinfunction "1_1") (pintype "passive"))
    )
    (net (code "41") (name "Net-(P6-Pad1)") (class "Default")
      (node (ref "P6") (pin "1") (pinfunction "1_1") (pintype "passive"))
      (node (ref "R51") (pin "2") (pinfunction "2_2") (pintype "passive"))
    )
    (net (code "42") (name "Net-(P6-Pad2)") (class "Default")
      (node (ref "P6") (pin "2") (pinfunction "2_2") (pintype "passive"))
      (node (ref "R15") (pin "1") (pinfunction "1_1") (pintype "passive"))
    )
    (net (code "43") (name "Net-(P6-Pad3)") (class "Default")
      (node (ref "P6") (pin "3") (pinfunction "3_3") (pintype "passive"))
      (node (ref "R52") (pin "1") (pinfunction "1_1") (pintype "passive"))
    )
    (net (code "44") (name "Net-(P7-Pad1)") (class "Default")
      (node (ref "P7") (pin "1") (pinfunction "1_1") (pintype "passive"))
      (node (ref "R53") (pin "2") (pinfunction "2_2") (pintype "passive"))
    )
    (net (code "45") (name "Net-(P7-Pad2)") (class "Default")
      (node (ref "P7") (pin "2") (pinfunction "2_2") (pintype "passive"))
      (node (ref "R27") (pin "1") (pinfunction "1_1") (pintype "passive"))
    )
    (net (code "46") (name "Net-(P7-Pad3)") (class "Default")
      (node (ref "P7") (pin "3") (pinfunction "3_3") (pintype "passive"))
      (node (ref "R54") (pin "1") (pinfunction "1_1") (pintype "passive"))
    )
    (net (code "47") (name "Net-(P8-Pad1)") (class "Default")
      (node (ref "P8") (pin "1") (pinfunction "1_1") (pintype "passive"))
      (node (ref "R55") (pin "2") (pinfunction "2_2") (pintype "passive"))
    )
    (net (code "48") (name "Net-(P8-Pad2)") (class "Default")
      (node (ref "P8") (pin "2") (pinfunction "2_2") (pintype "passive"))
      (node (ref "R39") (pin "1") (pinfunction "1_1") (pintype "passive"))
    )
    (net (code "49") (name "Net-(P8-Pad3)") (class "Default")
      (node (ref "P8") (pin "3") (pinfunction "3_3") (pintype "passive"))
      (node (ref "R56") (pin "1") (pinfunction "1_1") (pintype "passive"))
    )
    (net (code "50") (name "Net-(R10-Pad2)") (class "Default")
      (node (ref "R10") (pin "2") (pinfunction "2_2") (pintype "passive"))
      (node (ref "R5") (pin "2") (pinfunction "2_2") (pintype "passive"))
      (node (ref "R6") (pin "1") (pinfunction "1_1") (pintype "passive"))
    )
    (net (code "51") (name "Net-(R17-Pad2)") (class "Default")
      (node (ref "R17") (pin "2") (pinfunction "2_2") (pintype "passive"))
      (node (ref "R18") (pin "1") (pinfunction "1_1") (pintype "passive"))
      (node (ref "R22") (pin "2") (pinfunction "2_2") (pintype "passive"))
    )
    (net (code "52") (name "Net-(R29-Pad2)") (class "Default")
      (node (ref "R29") (pin "2") (pinfunction "2_2") (pintype "passive"))
      (node (ref "R30") (pin "1") (pinfunction "1_1") (pintype "passive"))
      (node (ref "R34") (pin "2") (pinfunction "2_2") (pintype "passive"))
    )
    (net (code "53") (name "Net-(R41-Pad2)") (class "Default")
      (node (ref "R41") (pin "2") (pinfunction "2_2") (pintype "passive"))
      (node (ref "R42") (pin "1") (pinfunction "1_1") (pintype "passive"))
      (node (ref "R46") (pin "2") (pinfunction "2_2") (pintype "passive"))
    )
    (net (code "54") (name "Net-(U1A-IN1-)") (class "Default")
      (node (ref "R1") (pin "1") (pinfunction "1_1") (pintype "passive"))
      (node (ref "R12") (pin "2") (pinfunction "2_2") (pintype "passive"))
      (node (ref "R3") (pin "2") (pinfunction "2_2") (pintype "passive"))
      (node (ref "R8") (pin "2") (pinfunction "2_2") (pintype "passive"))
      (node (ref "U1") (pin "2") (pinfunction "IN1-_2") (pintype "input"))
    )
    (net (code "55") (name "Net-(U1A-OUT1)") (class "Default")
      (node (ref "R1") (pin "2") (pinfunction "2_2") (pintype "passive"))
      (node (ref "R4") (pin "1") (pinfunction "1_1") (pintype "passive"))
      (node (ref "U1") (pin "1") (pinfunction "OUT1_1") (pintype "output"))
    )
    (net (code "56") (name "Net-(U1B-IN2-)") (class "Default")
      (node (ref "R14") (pin "1") (pinfunction "1_1") (pintype "passive"))
      (node (ref "R15") (pin "2") (pinfunction "2_2") (pintype "passive"))
      (node (ref "R20") (pin "2") (pinfunction "2_2") (pintype "passive"))
      (node (ref "R24") (pin "2") (pinfunction "2_2") (pintype "passive"))
      (node (ref "U1") (pin "6") (pinfunction "IN2-_6") (pintype "input"))
    )
    (net (code "57") (name "Net-(U1B-OUT2)") (class "Default")
      (node (ref "R14") (pin "2") (pinfunction "2_2") (pintype "passive"))
      (node (ref "R16") (pin "1") (pinfunction "1_1") (pintype "passive"))
      (node (ref "U1") (pin "7") (pinfunction "OUT2_7") (pintype "output"))
    )
    (net (code "58") (name "Net-(U2A-IN1-)") (class "Default")
      (node (ref "R26") (pin "1") (pinfunction "1_1") (pintype "passive"))
      (node (ref "R27") (pin "2") (pinfunction "2_2") (pintype "passive"))
      (node (ref "R32") (pin "2") (pinfunction "2_2") (pintype "passive"))
      (node (ref "R36") (pin "2") (pinfunction "2_2") (pintype "passive"))
      (node (ref "U2") (pin "2") (pinfunction "IN1-_2") (pintype "input"))
    )
    (net (code "59") (name "Net-(U2A-OUT1)") (class "Default")
      (node (ref "R26") (pin "2") (pinfunction "2_2") (pintype "passive"))
      (node (ref "R28") (pin "1") (pinfunction "1_1") (pintype "passive"))
      (node (ref "U2") (pin "1") (pinfunction "OUT1_1") (pintype "output"))
    )
    (net (code "60") (name "Net-(U2B-IN2-)") (class "Default")
      (node (ref "R38") (pin "1") (pinfunction "1_1") (pintype "passive"))
      (node (ref "R39") (pin "2") (pinfunction "2_2") (pintype "passive"))
      (node (ref "R44") (pin "2") (pinfunction "2_2") (pintype "passive"))
      (node (ref "R48") (pin "2") (pinfunction "2_2") (pintype "passive"))
      (node (ref "U2") (pin "6") (pinfunction "IN2-_6") (pintype "input"))
    )
    (net (code "61") (name "Net-(U2B-OUT2)") (class "Default")
      (node (ref "R38") (pin "2") (pinfunction "2_2") (pintype "passive"))
      (node (ref "R40") (pin "1") (pinfunction "1_1") (pintype "passive"))
      (node (ref "U2") (pin "7") (pinfunction "OUT2_7") (pintype "output"))
    )
    (net (code "62") (name "Net-(U3A-OUT1)") (class "Default")
      (node (ref "C1") (pin "2") (pinfunction "2_2") (pintype "passive"))
      (node (ref "R2") (pin "1") (pinfunction "1_1") (pintype "passive"))
      (node (ref "R7") (pin "2") (pinfunction "2_2") (pintype "passive"))
      (node (ref "R9") (pin "2") (pinfunction "2_2") (pintype "passive"))
      (node (ref "U3") (pin "1") (pinfunction "OUT1_1") (pintype "output"))
    )
    (net (code "63") (name "Net-(U3B-OUT2)") (class "Default")
      (node (ref "C3") (pin "2") (pinfunction "2_2") (pintype "passive"))
      (node (ref "R13") (pin "1") (pinfunction "1_1") (pintype "passive"))
      (node (ref "R19") (pin "2") (pinfunction "2_2") (pintype "passive"))
      (node (ref "R21") (pin "2") (pinfunction "2_2") (pintype "passive"))
      (node (ref "U3") (pin "7") (pinfunction "OUT2_7") (pintype "output"))
    )
    (net (code "64") (name "Net-(U4A-OUT1)") (class "Default")
      (node (ref "C5") (pin "2") (pinfunction "2_2") (pintype "passive"))
      (node (ref "R25") (pin "1") (pinfunction "1_1") (pintype "passive"))
      (node (ref "R31") (pin "2") (pinfunction "2_2") (pintype "passive"))
      (node (ref "R33") (pin "2") (pinfunction "2_2") (pintype "passive"))
      (node (ref "U4") (pin "1") (pinfunction "OUT1_1") (pintype "output"))
    )
    (net (code "65") (name "Net-(U4B-OUT2)") (class "Default")
      (node (ref "C7") (pin "2") (pinfunction "2_2") (pintype "passive"))
      (node (ref "R37") (pin "1") (pinfunction "1_1") (pintype "passive"))
      (node (ref "R43") (pin "2") (pinfunction "2_2") (pintype "passive"))
      (node (ref "R45") (pin "2") (pinfunction "2_2") (pintype "passive"))
      (node (ref "U4") (pin "7") (pinfunction "OUT2_7") (pintype "output"))
    )
    (net (code "66") (name "unconnected-(IC1E-MODE-Pad1)") (class "Default")
      (node (ref "IC1") (pin "1") (pinfunction "MODE_1") (pintype "passive"))
    )
    (net (code "67") (name "unconnected-(P4-Pad11)") (class "Default")
      (node (ref "P4") (pin "11") (pinfunction "11_11") (pintype "passive"))
    )
    (net (code "68") (name "unconnected-(P4-Pad12)") (class "Default")
      (node (ref "P4") (pin "12") (pinfunction "12_12") (pintype "passive"))
    )
    (net (code "69") (name "unconnected-(P4-Pad13)") (class "Default")
      (node (ref "P4") (pin "13") (pinfunction "13_13") (pintype "passive"))
    )
    (net (code "70") (name "unconnected-(P4-Pad14)") (class "Default")
      (node (ref "P4") (pin "14") (pinfunction "14_14") (pintype "passive"))
    )
    (net (code "71") (name "unconnected-(P4-Pad15)") (class "Default")
      (node (ref "P4") (pin "15") (pinfunction "15_15") (pintype "passive"))
    )
    (net (code "72") (name "unconnected-(P4-Pad16)") (class "Default")
      (node (ref "P4") (pin "16") (pinfunction "16_16") (pintype "passive"))
    )
  )
)
